# ProgAdapter.net
KiCad netlist of a schematic drawn in EAGLE
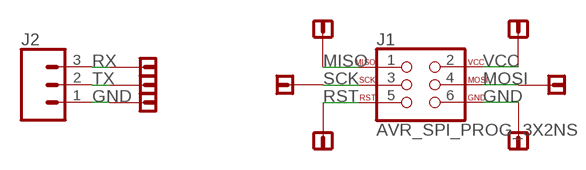
[diagram p0: schematic, sheet 1]

(export (version "E")
  (design (tool "Eeschema 10.0.6"))
  (components
    (comp (ref "J1")
      (value "AVR_SPI_PROG_3X2NS")
      (footprint "eagle-import:2X3-NS")
      (libsource (lib "eagle-import") (part "AVR_SPI_PROG_3X2NS"))
    )
    (comp (ref "J2")
      (value "CONN_03")
      (footprint "eagle-import:1X03")
      (libsource (lib "eagle-import") (part "CONN_03"))
    )
    (comp (ref "U$1")
      (value "SIMPLE_VIA_CONNECTION")
      (footprint "eagle-import:SIMPLEVIA")
      (libsource (lib "eagle-import") (part "SIMPLE_VIA_CONNECTION"))
    )
    (comp (ref "U$2")
      (value "SIMPLE_VIA_CONNECTION")
      (footprint "eagle-import:SIMPLEVIA")
      (libsource (lib "eagle-import") (part "SIMPLE_VIA_CONNECTION"))
    )
    (comp (ref "U$3")
      (value "SIMPLE_VIA_CONNECTION")
      (footprint "eagle-import:SIMPLEVIA")
      (libsource (lib "eagle-import") (part "SIMPLE_VIA_CONNECTION"))
    )
    (comp (ref "U$4")
      (value "SIMPLE_VIA_CONNECTION")
      (footprint "eagle-import:SIMPLEVIA")
      (libsource (lib "eagle-import") (part "SIMPLE_VIA_CONNECTION"))
    )
    (comp (ref "U$5")
      (value "SIMPLE_VIA_CONNECTION")
      (footprint "eagle-import:SIMPLEVIA")
      (libsource (lib "eagle-import") (part "SIMPLE_VIA_CONNECTION"))
    )
    (comp (ref "U$6")
      (value "SIMPLE_VIA_CONNECTION")
      (footprint "eagle-import:SIMPLEVIA")
      (libsource (lib "eagle-import") (part "SIMPLE_VIA_CONNECTION"))
    )
    (comp (ref "U$7")
      (value "SIMPLE_VIA_CONNECTION")
      (footprint "eagle-import:SIMPLEVIA")
      (libsource (lib "eagle-import") (part "SIMPLE_VIA_CONNECTION"))
    )
    (comp (ref "U$8")
      (value "SIMPLE_VIA_CONNECTION")
      (footprint "eagle-import:SIMPLEVIA")
      (libsource (lib "eagle-import") (part "SIMPLE_VIA_CONNECTION"))
    )
    (comp (ref "U$9")
      (value "SIMPLE_VIA_CONNECTION")
      (footprint "eagle-import:SIMPLEVIA")
      (libsource (lib "eagle-import") (part "SIMPLE_VIA_CONNECTION"))
    )
  )
  (nets
    (net (code "1") (name "/GND") (class "Default")
      (node (ref "J1") (pin "6") (pinfunction "6_6") (pintype "passive"))
      (node (ref "J2") (pin "1") (pinfunction "1_1") (pintype "passive"))
      (node (ref "U$4") (pin "P$1") (pinfunction "1_P$1") (pintype "passive"))
      (node (ref "U$9") (pin "P$1") (pinfunction "1_P$1") (pintype "passive"))
    )
    (net (code "2") (name "/MISO") (class "Default")
      (node (ref "J1") (pin "1") (pinfunction "1_1") (pintype "passive"))
      (node (ref "U$1") (pin "P$1") (pinfunction "1_P$1") (pintype "passive"))
    )
    (net (code "3") (name "/MOSI") (class "Default")
      (node (ref "J1") (pin "4") (pinfunction "4_4") (pintype "passive"))
      (node (ref "U$5") (pin "P$1") (pinfunction "1_P$1") (pintype "passive"))
    )
    (net (code "4") (name "/RST") (class "Default")
      (node (ref "J1") (pin "5") (pinfunction "5_5") (pintype "passive"))
      (node (ref "U$3") (pin "P$1") (pinfunction "1_P$1") (pintype "passive"))
    )
    (net (code "5") (name "/RX") (class "Default")
      (node (ref "J2") (pin "3") (pinfunction "3_3") (pintype "passive"))
      (node (ref "U$7") (pin "P$1") (pinfunction "1_P$1") (pintype "passive"))
    )
    (net (code "6") (name "/SCK") (class "Default")
      (node (ref "J1") (pin "3") (pinfunction "3_3") (pintype "passive"))
      (node (ref "U$2") (pin "P$1") (pinfunction "1_P$1") (pintype "passive"))
    )
    (net (code "7") (name "/TX") (class "Default")
      (node (ref "J2") (pin "2") (pinfunction "2_2") (pintype "passive"))
      (node (ref "U$8") (pin "P$1") (pinfunction "1_P$1") (pintype "passive"))
    )
    (net (code "8") (name "/VCC") (class "Default")
      (node (ref "J1") (pin "2") (pinfunction "2_2") (pintype "passive"))
      (node (ref "U$6") (pin "P$1") (pinfunction "1_P$1") (pintype "passive"))
    )
  )
)
